# SensWear_RGB.net
KiCad netlist of a schematic drawn in Altium Designer
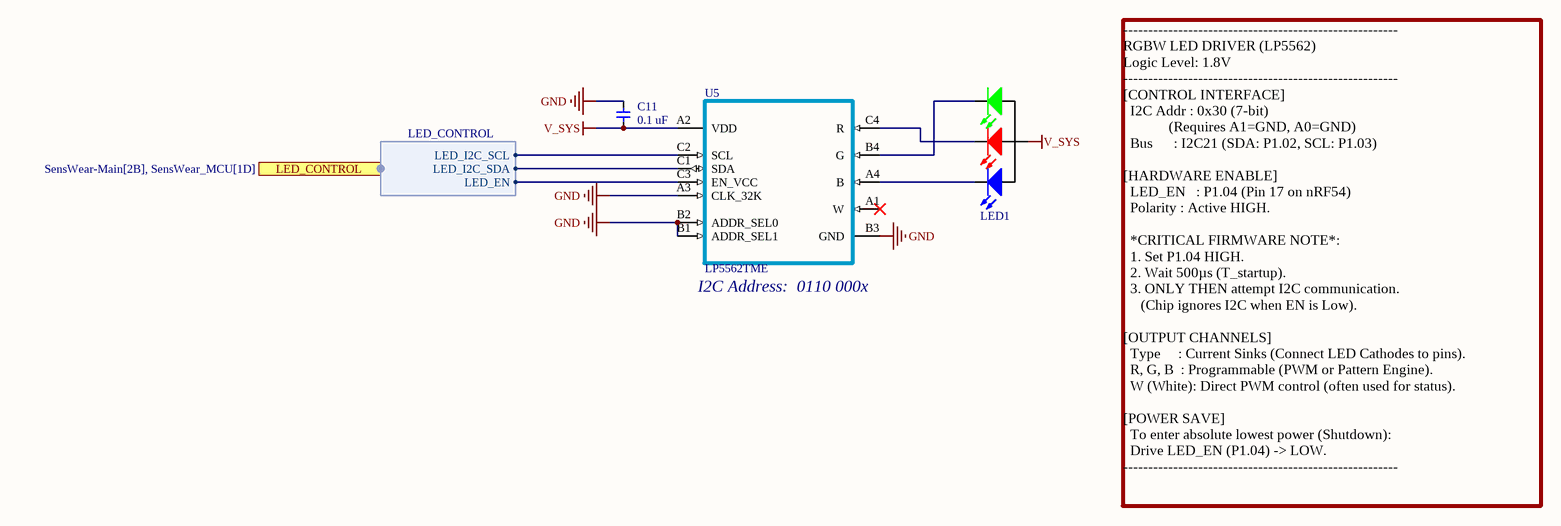
[diagram p0: SensWear_RGB.SchDoc]

(export (version "E")
  (design (tool "Eeschema 10.0.6"))
  (components
    (comp (ref "C11")
      (value "0.1 uF")
      (footprint "CAPC1005X05N")
      (description "CAP CER 0.1UF 16V X5R 0402")
      (fields
        (field (name "MANUFACTURER") "Murata Electronics")
        (field (name "MANUFACTURER PART NUMBER") "GRM155R61C104KA88D")
      )
      (libsource (lib "SensWearComponents") (part "GRM155R61C104KA88D__2"))
    )
    (comp (ref "LED1")
      (value "SML-LX0404SIUPGUSB")
      (footprint "SML-LX0404SIUPGUSB")
      (description "LED Low-Power Tri-Color Blue/Green/Red 465nm/518nm/632nm 2.7V/2.75V/1.95V 4-Pin SMD T/R")
      (fields (field (name "MANUFACTURER") "Lumex"))
      (libsource (lib "SensWearComponents") (part "SML-LX0404SIUPGUSB"))
    )
    (comp (ref "U5")
      (value "LP5562TME")
      (footprint "BGA12C40P4X3_162X122X68")
      (description "IC LED DRIVER LINEAR DIM 25.5MA")
      (fields
        (field (name "MANUFACTURER") "Texas Instruments")
        (field (name "MANUFACTURER PART NUMBER") "LP5562TME/NOPB")
      )
      (libsource (lib "SensWearComponents") (part "LP5562TME/NOPB"))
    )
  )
  (nets
    (net (code "2") (name "/LED_EN") (class "Default")
      (node (ref "U5") (pin "C3") (pinfunction "EN_VCC_C3") (pintype "input"))
    )
    (net (code "3") (name "/LED_I2C_SCL") (class "Default")
      (node (ref "U5") (pin "C2") (pinfunction "SCL_C2") (pintype "input"))
    )
    (net (code "4") (name "/LED_I2C_SDA") (class "Default")
      (node (ref "U5") (pin "C1") (pinfunction "SDA_C1") (pintype "bidirectional"))
    )
    (net (code "6") (name "GND") (class "Default")
      (node (ref "C11") (pin "2") (pinfunction "2_2") (pintype "passive"))
      (node (ref "U5") (pin "A3") (pinfunction "CLK_32K_A3") (pintype "input"))
      (node (ref "U5") (pin "B1") (pinfunction "ADDR_SEL1_B1") (pintype "input"))
      (node (ref "U5") (pin "B2") (pinfunction "ADDR_SEL0_B2") (pintype "input"))
      (node (ref "U5") (pin "B3") (pinfunction "GND_B3") (pintype "power_in"))
    )
    (net (code "7") (name "Net-(U5-B)") (class "Default")
      (node (ref "LED1") (pin "3") (pinfunction "K_3") (pintype "passive"))
      (node (ref "U5") (pin "A4") (pinfunction "B_A4") (pintype "input"))
    )
    (net (code "8") (name "Net-(U5-G)") (class "Default")
      (node (ref "LED1") (pin "4") (pinfunction "K_4") (pintype "passive"))
      (node (ref "U5") (pin "B4") (pinfunction "G_B4") (pintype "input"))
    )
    (net (code "9") (name "Net-(U5-R)") (class "Default")
      (node (ref "LED1") (pin "2") (pinfunction "K_2") (pintype "passive"))
      (node (ref "U5") (pin "C4") (pinfunction "R_C4") (pintype "input"))
    )
    (net (code "10") (name "V_SYS") (class "Default")
      (node (ref "C11") (pin "1") (pinfunction "1_1") (pintype "passive"))
      (node (ref "LED1") (pin "1") (pinfunction "A_1") (pintype "passive"))
      (node (ref "U5") (pin "A2") (pinfunction "VDD_A2") (pintype "power_in"))
    )
    (net (code "11") (name "unconnected-(U5-W-PadA1)") (class "Default")
      (node (ref "U5") (pin "A1") (pinfunction "W_A1") (pintype "input+no_connect"))
    )
  )
)
